# LiPoBatteryBreadboardSupply.net
KiCad netlist of a schematic drawn in EAGLE
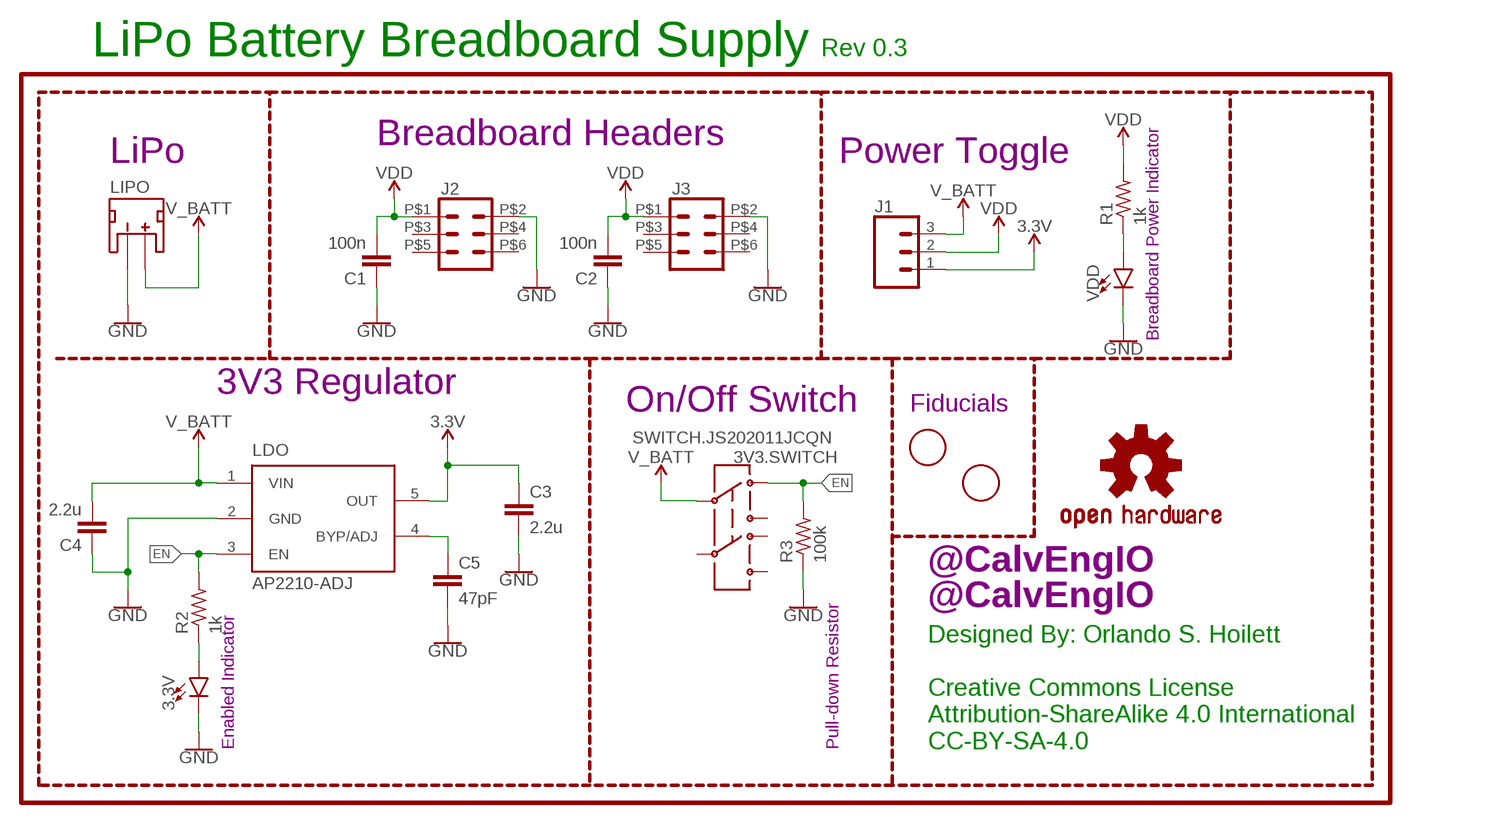
[diagram p0: schematic, sheet 1]

(export (version "E")
  (design (tool "Eeschema 10.0.6"))
  (components
    (comp (ref "3.3V")
      (value "LED0603")
      (footprint "eagle-import:LED-0603")
      (libsource (lib "eagle-import") (part "LED0603"))
    )
    (comp (ref "3V3.SWITCH")
      (value "SWITCH.JS202011JCQN")
      (footprint "eagle-import:SWITCH.00")
      (libsource (lib "eagle-import") (part "SWITCH.JS202011JCQN"))
    )
    (comp (ref "C1")
      (value "100n")
      (footprint "eagle-import:C0603")
      (libsource (lib "eagle-import") (part "CAPACITOR0603"))
    )
    (comp (ref "C2")
      (value "100n")
      (footprint "eagle-import:C0603")
      (libsource (lib "eagle-import") (part "CAPACITOR0603"))
    )
    (comp (ref "C3")
      (value "2.2u")
      (footprint "eagle-import:C0603")
      (libsource (lib "eagle-import") (part "C-EUC0603"))
    )
    (comp (ref "C4")
      (value "2.2u")
      (footprint "eagle-import:C0603")
      (libsource (lib "eagle-import") (part "C-EUC0603"))
    )
    (comp (ref "C5")
      (value "47pF")
      (footprint "eagle-import:C0402")
      (libsource (lib "eagle-import") (part "C-EUC0402"))
    )
    (comp (ref "FD1")
      (value "FIDUCIAL")
      (footprint "eagle-import:FIDUCIAL_1MM")
      (libsource (lib "eagle-import") (part "FIDUCIAL"))
    )
    (comp (ref "FD2")
      (value "FIDUCIAL")
      (footprint "eagle-import:FIDUCIAL_1MM")
      (libsource (lib "eagle-import") (part "FIDUCIAL"))
    )
    (comp (ref "J1")
      (value "CONN_03")
      (footprint "eagle-import:1X03")
      (libsource (lib "eagle-import") (part "CONN_03"))
    )
    (comp (ref "J2")
      (value "JMP.03X2HEADERS")
      (footprint "eagle-import:JMP.03X2")
      (libsource (lib "eagle-import") (part "JMP.03X2HEADERS"))
    )
    (comp (ref "J3")
      (value "JMP.03X2HEADERS")
      (footprint "eagle-import:JMP.03X2")
      (libsource (lib "eagle-import") (part "JMP.03X2HEADERS"))
    )
    (comp (ref "LDO")
      (value "AP2210-ADJ")
      (footprint "eagle-import:SOT23-5")
      (libsource (lib "eagle-import") (part "AP2210-ADJ"))
    )
    (comp (ref "LIPO")
      (value "JST_2MM_MALE")
      (footprint "eagle-import:JST-2-SMD")
      (libsource (lib "eagle-import") (part "JST_2MM_MALE"))
    )
    (comp (ref "LOGO1")
      (value "OSHW-LOGOS")
      (footprint "eagle-import:OSHW-LOGO-S")
      (libsource (lib "eagle-import") (part "OSHW-LOGOS"))
    )
    (comp (ref "R1")
      (value "1k")
      (footprint "eagle-import:R0402")
      (libsource (lib "eagle-import") (part "R-US_R0402"))
    )
    (comp (ref "R2")
      (value "1k")
      (footprint "eagle-import:R0402")
      (libsource (lib "eagle-import") (part "R-US_R0402"))
    )
    (comp (ref "R3")
      (value "100k")
      (footprint "eagle-import:R0402")
      (libsource (lib "eagle-import") (part "R-US_R0402"))
    )
    (comp (ref "U$1")
      (value "HANDLE.1HANDLE.025")
      (footprint "eagle-import:HANDLE.025")
      (libsource (lib "eagle-import") (part "HANDLE.1HANDLE.025"))
    )
    (comp (ref "U$6")
      (value "HANDLE.1HANDLE.08")
      (footprint "eagle-import:HANDLE.08")
      (libsource (lib "eagle-import") (part "HANDLE.1HANDLE.08"))
    )
    (comp (ref "VDD")
      (value "LED0603")
      (footprint "eagle-import:LED-0603")
      (libsource (lib "eagle-import") (part "LED0603"))
    )
  )
  (nets
    (net (code "1") (name "3.3V") (class "Default")
      (node (ref "C3") (pin "1") (pinfunction "1_1") (pintype "passive"))
      (node (ref "J1") (pin "1") (pinfunction "1_1") (pintype "passive"))
      (node (ref "LDO") (pin "5") (pinfunction "OUT_5") (pintype "bidirectional"))
    )
    (net (code "2") (name "EN") (class "Default")
      (node (ref "3V3.SWITCH") (pin "1") (pinfunction "1_1") (pintype "bidirectional"))
      (node (ref "LDO") (pin "3") (pinfunction "EN_3") (pintype "bidirectional"))
      (node (ref "R2") (pin "2") (pinfunction "2_2") (pintype "passive"))
      (node (ref "R3") (pin "2") (pinfunction "2_2") (pintype "passive"))
    )
    (net (code "3") (name "GND") (class "Default")
      (node (ref "3.3V") (pin "C") (pinfunction "C_C") (pintype "passive"))
      (node (ref "C1") (pin "1") (pinfunction "1_1") (pintype "passive"))
      (node (ref "C2") (pin "1") (pinfunction "1_1") (pintype "passive"))
      (node (ref "C3") (pin "2") (pinfunction "2_2") (pintype "passive"))
      (node (ref "C4") (pin "1") (pinfunction "1_1") (pintype "passive"))
      (node (ref "C5") (pin "2") (pinfunction "2_2") (pintype "passive"))
      (node (ref "J2") (pin "P$2") (pinfunction "2_P$2") (pintype "bidirectional"))
      (node (ref "J3") (pin "P$2") (pinfunction "2_P$2") (pintype "bidirectional"))
      (node (ref "LDO") (pin "2") (pinfunction "GND_2") (pintype "bidirectional"))
      (node (ref "LIPO") (pin "1") (pinfunction "-_1") (pintype "bidirectional"))
      (node (ref "R3") (pin "1") (pinfunction "1_1") (pintype "passive"))
      (node (ref "VDD") (pin "C") (pinfunction "C_C") (pintype "passive"))
    )
    (net (code "4") (name "Net-(3.3V-PadA)") (class "Default")
      (node (ref "3.3V") (pin "A") (pinfunction "A_A") (pintype "passive"))
      (node (ref "R2") (pin "1") (pinfunction "1_1") (pintype "passive"))
    )
    (net (code "5") (name "Net-(LDO-BYP{slash}ADJ)") (class "Default")
      (node (ref "C5") (pin "1") (pinfunction "1_1") (pintype "passive"))
      (node (ref "LDO") (pin "4") (pinfunction "BYP/ADJ_4") (pintype "bidirectional"))
    )
    (net (code "6") (name "Net-(R1-Pad1)") (class "Default")
      (node (ref "R1") (pin "1") (pinfunction "1_1") (pintype "passive"))
      (node (ref "VDD") (pin "A") (pinfunction "A_A") (pintype "passive"))
    )
    (net (code "7") (name "VDD") (class "Default")
      (node (ref "C1") (pin "2") (pinfunction "2_2") (pintype "passive"))
      (node (ref "C2") (pin "2") (pinfunction "2_2") (pintype "passive"))
      (node (ref "J1") (pin "2") (pinfunction "2_2") (pintype "passive"))
      (node (ref "J2") (pin "P$1") (pinfunction "1_P$1") (pintype "bidirectional"))
      (node (ref "J3") (pin "P$1") (pinfunction "1_P$1") (pintype "bidirectional"))
      (node (ref "R1") (pin "2") (pinfunction "2_2") (pintype "passive"))
    )
    (net (code "8") (name "V_BATT") (class "Default")
      (node (ref "3V3.SWITCH") (pin "2") (pinfunction "2_2") (pintype "bidirectional"))
      (node (ref "C4") (pin "2") (pinfunction "2_2") (pintype "passive"))
      (node (ref "J1") (pin "3") (pinfunction "3_3") (pintype "passive"))
      (node (ref "LDO") (pin "1") (pinfunction "VIN_1") (pintype "bidirectional"))
      (node (ref "LIPO") (pin "2") (pinfunction "+_2") (pintype "bidirectional"))
    )
    (net (code "9") (name "unconnected-(3V3.SWITCH-Pad3)") (class "Default")
      (node (ref "3V3.SWITCH") (pin "3") (pinfunction "3_3") (pintype "bidirectional"))
    )
    (net (code "10") (name "unconnected-(3V3.SWITCH-Pad5)") (class "Default")
      (node (ref "3V3.SWITCH") (pin "5") (pinfunction "5_5") (pintype "bidirectional"))
    )
    (net (code "11") (name "unconnected-(3V3.SWITCH-Pad6)") (class "Default")
      (node (ref "3V3.SWITCH") (pin "6") (pinfunction "6_6") (pintype "bidirectional"))
    )
    (net (code "12") (name "unconnected-(3V3.SWITCH-Pad7)") (class "Default")
      (node (ref "3V3.SWITCH") (pin "7") (pinfunction "7_7") (pintype "bidirectional"))
    )
    (net (code "13") (name "unconnected-(J2-3-PadP$3)") (class "Default")
      (node (ref "J2") (pin "P$3") (pinfunction "3_P$3") (pintype "bidirectional"))
    )
    (net (code "14") (name "unconnected-(J2-4-PadP$4)") (class "Default")
      (node (ref "J2") (pin "P$4") (pinfunction "4_P$4") (pintype "bidirectional"))
    )
    (net (code "15") (name "unconnected-(J2-5-PadP$5)") (class "Default")
      (node (ref "J2") (pin "P$5") (pinfunction "5_P$5") (pintype "bidirectional"))
    )
    (net (code "16") (name "unconnected-(J2-6-PadP$6)") (class "Default")
      (node (ref "J2") (pin "P$6") (pinfunction "6_P$6") (pintype "bidirectional"))
    )
    (net (code "17") (name "unconnected-(J3-3-PadP$3)") (class "Default")
      (node (ref "J3") (pin "P$3") (pinfunction "3_P$3") (pintype "bidirectional"))
    )
    (net (code "18") (name "unconnected-(J3-4-PadP$4)") (class "Default")
      (node (ref "J3") (pin "P$4") (pinfunction "4_P$4") (pintype "bidirectional"))
    )
    (net (code "19") (name "unconnected-(J3-5-PadP$5)") (class "Default")
      (node (ref "J3") (pin "P$5") (pinfunction "5_P$5") (pintype "bidirectional"))
    )
    (net (code "20") (name "unconnected-(J3-6-PadP$6)") (class "Default")
      (node (ref "J3") (pin "P$6") (pinfunction "6_P$6") (pintype "bidirectional"))
    )
    (net (code "21") (name "unconnected-(LIPO-PAD1-PadNC1)") (class "Default")
      (node (ref "LIPO") (pin "NC1") (pinfunction "PAD1_NC1") (pintype "bidirectional"))
    )
    (net (code "22") (name "unconnected-(LIPO-PAD2-PadNC2)") (class "Default")
      (node (ref "LIPO") (pin "NC2") (pinfunction "PAD2_NC2") (pintype "bidirectional"))
    )
  )
)
